# USBSocket_Type6_v1_0.net
KiCad netlist of a schematic drawn in EAGLE
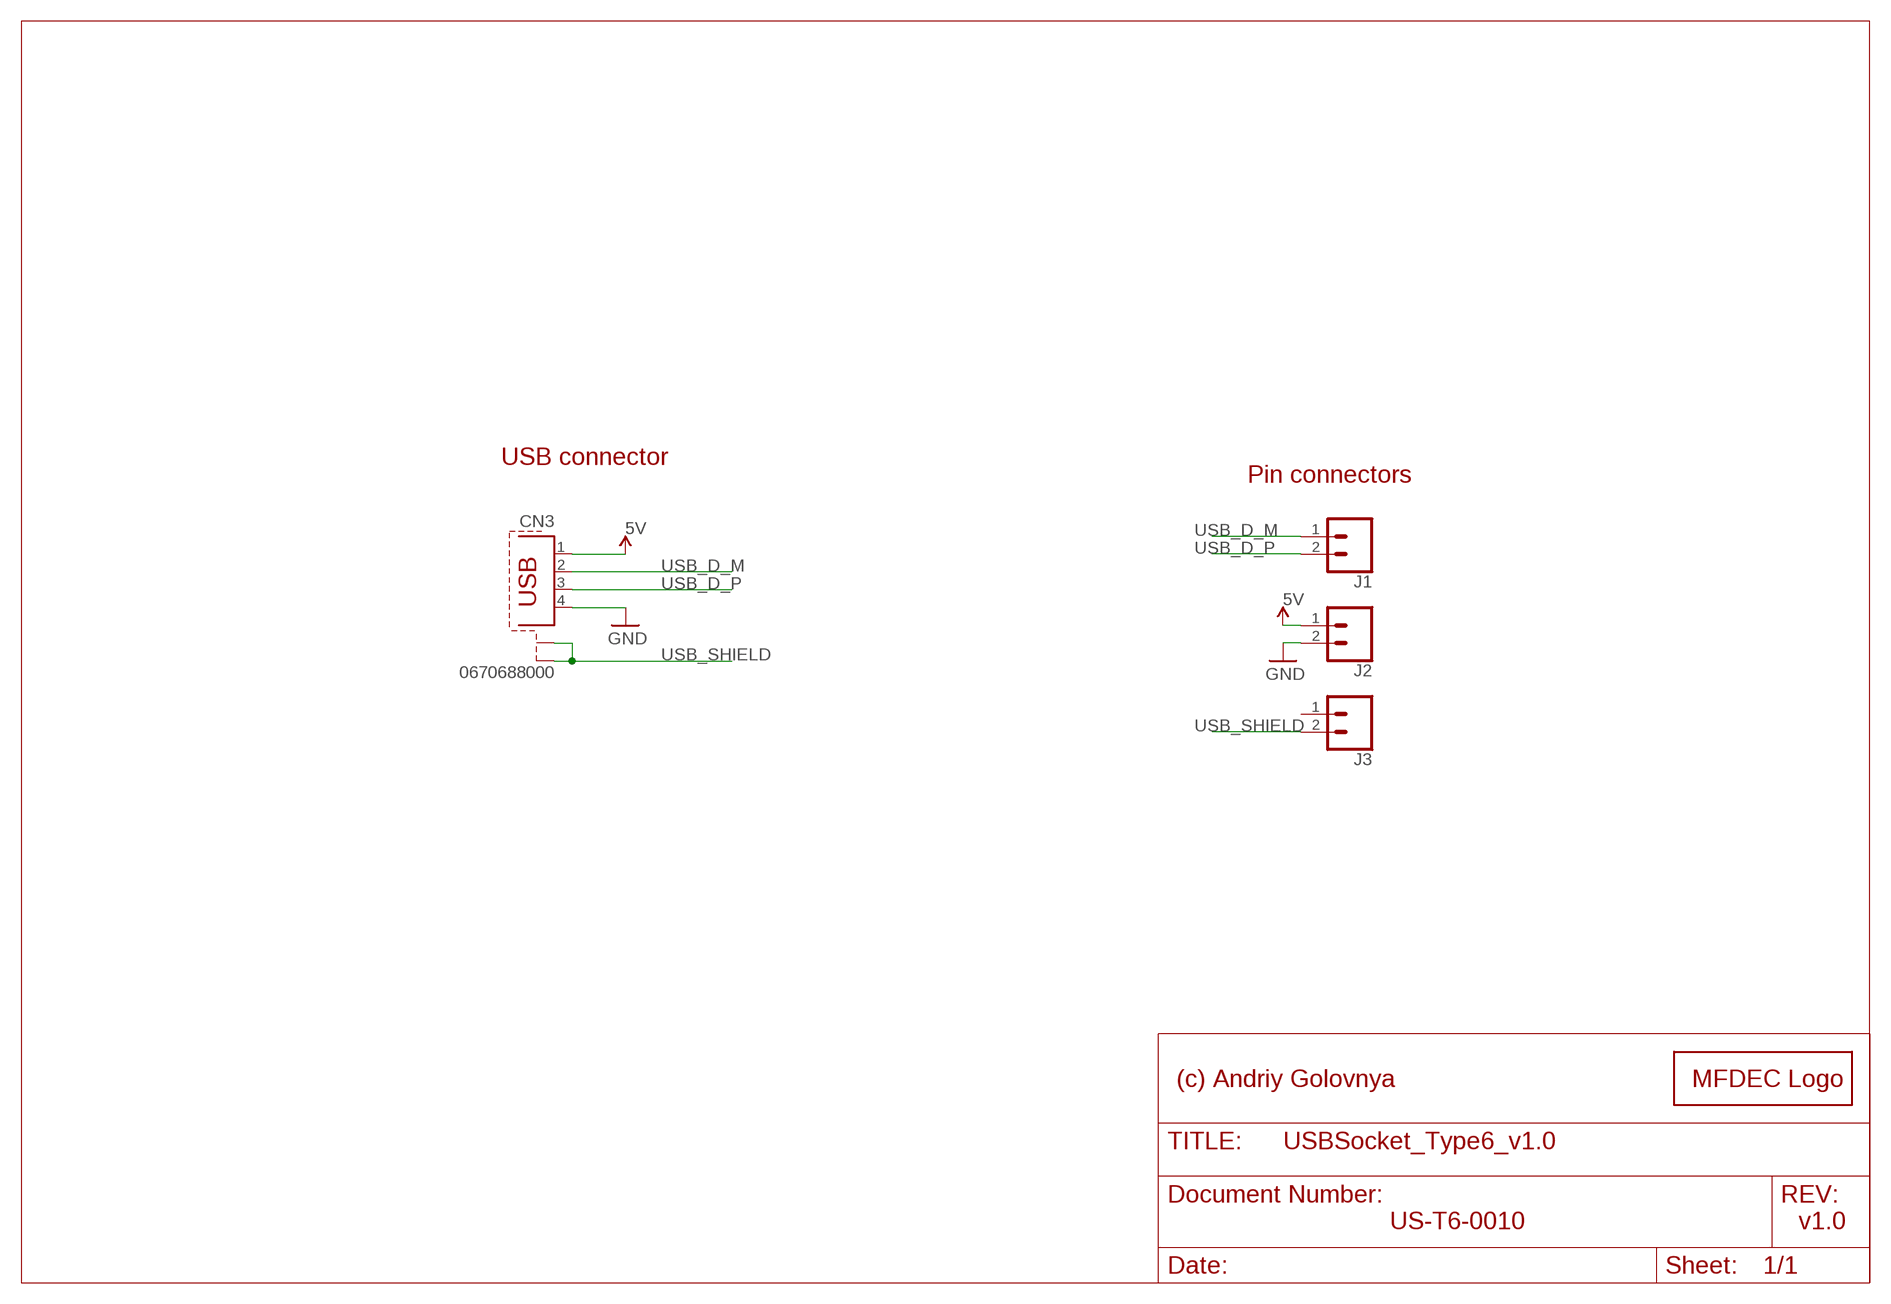
[diagram p0: schematic, sheet 1]

(export (version "E")
  (design (tool "Eeschema 10.0.6"))
  (components
    (comp (ref "CN3")
      (value "0670688000")
      (footprint "eagle-import:PN61729-S")
      (libsource (lib "eagle-import") (part "PN61729-S"))
    )
    (comp (ref "J1")
      (value "CONN_02")
      (footprint "eagle-import:1X02")
      (libsource (lib "eagle-import") (part "CONN_02"))
    )
    (comp (ref "J2")
      (value "CONN_02")
      (footprint "eagle-import:1X02")
      (libsource (lib "eagle-import") (part "CONN_02"))
    )
    (comp (ref "J3")
      (value "CONN_02")
      (footprint "eagle-import:1X02")
      (libsource (lib "eagle-import") (part "CONN_02"))
    )
    (comp (ref "LOGO1")
      (value "MFDECLOGO_L_10MM")
      (footprint "eagle-import:MFDEC_L_10MM")
      (libsource (lib "eagle-import") (part "MFDECLOGO_L_10MM"))
    )
  )
  (nets
    (net (code "1") (name "/USB_D_M") (class "Default")
      (node (ref "CN3") (pin "2") (pinfunction "2_2") (pintype "passive"))
      (node (ref "J1") (pin "1") (pinfunction "1_1") (pintype "passive"))
    )
    (net (code "2") (name "/USB_D_P") (class "Default")
      (node (ref "CN3") (pin "3") (pinfunction "3_3") (pintype "passive"))
      (node (ref "J1") (pin "2") (pinfunction "2_2") (pintype "passive"))
    )
    (net (code "3") (name "/USB_SHIELD") (class "Default")
      (node (ref "CN3") (pin "S1") (pinfunction "S1_S1") (pintype "passive"))
      (node (ref "CN3") (pin "S2") (pinfunction "S2_S2") (pintype "passive"))
      (node (ref "J3") (pin "2") (pinfunction "2_2") (pintype "passive"))
    )
    (net (code "4") (name "5V") (class "Default")
      (node (ref "CN3") (pin "1") (pinfunction "1_1") (pintype "passive"))
      (node (ref "J2") (pin "1") (pinfunction "1_1") (pintype "passive"))
    )
    (net (code "5") (name "GND") (class "Default")
      (node (ref "CN3") (pin "4") (pinfunction "4_4") (pintype "passive"))
      (node (ref "J2") (pin "2") (pinfunction "2_2") (pintype "passive"))
    )
    (net (code "6") (name "unconnected-(J3-Pad1)") (class "Default")
      (node (ref "J3") (pin "1") (pinfunction "1_1") (pintype "passive"))
    )
  )
)
